# Zigzag_6p_ATtiny_connector.net
KiCad netlist of a schematic drawn in EAGLE
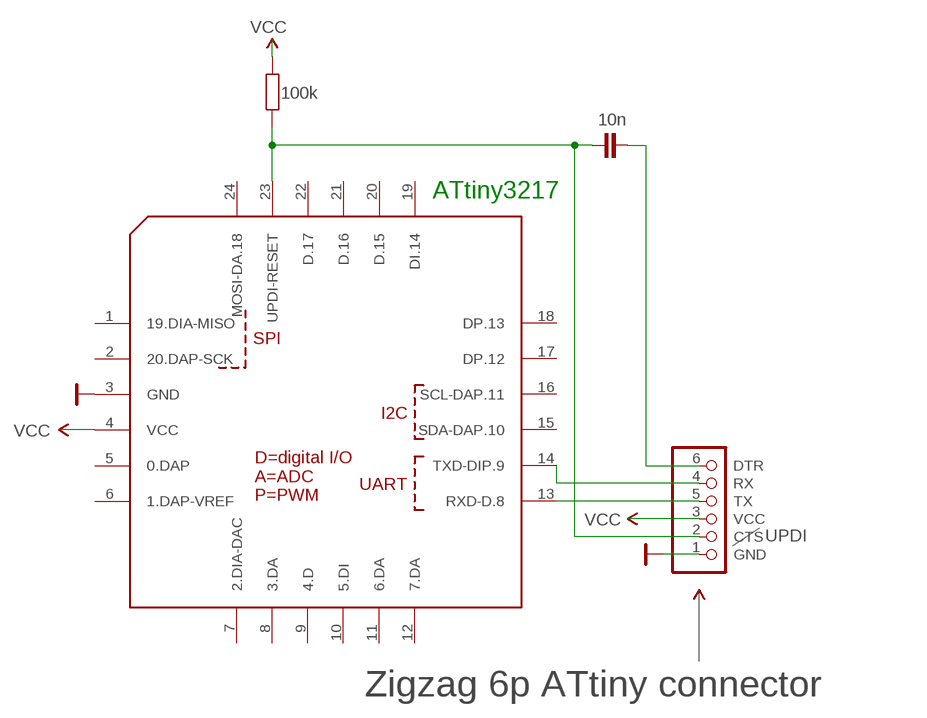
[diagram p0: schematic, sheet 1]

(export (version "E")
  (design (tool "Eeschema 10.0.6"))
  (components
    (comp (ref "C2")
      (value "10n")
      (footprint "eagle-import:0603-SMALL")
      (libsource (lib "eagle-import") (part "SMD-C-0603-SMALL"))
    )
    (comp (ref "J2")
      (value "FTDI")
      (footprint "eagle-import:ZIGZAG-FTDI")
      (libsource (lib "eagle-import") (part "FTDI"))
    )
    (comp (ref "R2")
      (value "100k")
      (footprint "eagle-import:0603-SMALL")
      (libsource (lib "eagle-import") (part "SMD-R0603-S"))
    )
    (comp (ref "U1")
      (value "ATTINY3217-")
      (footprint "eagle-import:QFN-24")
      (libsource (lib "eagle-import") (part "ATTINY3217-"))
    )
  )
  (nets
    (net (code "1") (name "/UPDI") (class "Default")
      (node (ref "C2") (pin "1") (pinfunction "1_1") (pintype "passive"))
      (node (ref "J2") (pin "2") (pinfunction "CTS_2") (pintype "passive"))
      (node (ref "R2") (pin "1") (pinfunction "1_1") (pintype "passive"))
      (node (ref "U1") (pin "23") (pinfunction "UPDI-RESET_23") (pintype "bidirectional"))
    )
    (net (code "2") (name "/VCC") (class "Default")
      (node (ref "J2") (pin "3") (pinfunction "VCC_3") (pintype "passive"))
      (node (ref "R2") (pin "2") (pinfunction "2_2") (pintype "passive"))
      (node (ref "U1") (pin "4") (pinfunction "VCC_4") (pintype "bidirectional"))
    )
    (net (code "3") (name "GND") (class "Default")
      (node (ref "J2") (pin "1") (pinfunction "GND_1") (pintype "passive"))
      (node (ref "U1") (pin "3") (pinfunction "GND_3") (pintype "bidirectional"))
    )
    (net (code "4") (name "Net-(J2-DTR)") (class "Default")
      (node (ref "C2") (pin "2") (pinfunction "2_2") (pintype "passive"))
      (node (ref "J2") (pin "6") (pinfunction "DTR_6") (pintype "passive"))
    )
    (net (code "5") (name "Net-(J2-RX)") (class "Default")
      (node (ref "J2") (pin "4") (pinfunction "RX_4") (pintype "passive"))
      (node (ref "U1") (pin "14") (pinfunction "TXD-DIP.9_14") (pintype "bidirectional"))
    )
    (net (code "6") (name "Net-(J2-TX)") (class "Default")
      (node (ref "J2") (pin "5") (pinfunction "TX_5") (pintype "passive"))
      (node (ref "U1") (pin "13") (pinfunction "RXD-D.8_13") (pintype "bidirectional"))
    )
    (net (code "7") (name "unconnected-(U1-0.DAP-Pad5)") (class "Default")
      (node (ref "U1") (pin "5") (pinfunction "0.DAP_5") (pintype "bidirectional"))
    )
    (net (code "8") (name "unconnected-(U1-1.DAP-VREF-Pad6)") (class "Default")
      (node (ref "U1") (pin "6") (pinfunction "1.DAP-VREF_6") (pintype "bidirectional"))
    )
    (net (code "9") (name "unconnected-(U1-2.DIA-DAC-Pad7)") (class "Default")
      (node (ref "U1") (pin "7") (pinfunction "2.DIA-DAC_7") (pintype "bidirectional"))
    )
    (net (code "10") (name "unconnected-(U1-3.DA-Pad8)") (class "Default")
      (node (ref "U1") (pin "8") (pinfunction "3.DA_8") (pintype "bidirectional"))
    )
    (net (code "11") (name "unconnected-(U1-4.D-Pad9)") (class "Default")
      (node (ref "U1") (pin "9") (pinfunction "4.D_9") (pintype "bidirectional"))
    )
    (net (code "12") (name "unconnected-(U1-5.DI-Pad10)") (class "Default")
      (node (ref "U1") (pin "10") (pinfunction "5.DI_10") (pintype "bidirectional"))
    )
    (net (code "13") (name "unconnected-(U1-6.DA-Pad11)") (class "Default")
      (node (ref "U1") (pin "11") (pinfunction "6.DA_11") (pintype "bidirectional"))
    )
    (net (code "14") (name "unconnected-(U1-7.DA-Pad12)") (class "Default")
      (node (ref "U1") (pin "12") (pinfunction "7.DA_12") (pintype "bidirectional"))
    )
    (net (code "15") (name "unconnected-(U1-19.DIA-MISO-Pad1)") (class "Default")
      (node (ref "U1") (pin "1") (pinfunction "19.DIA-MISO_1") (pintype "bidirectional"))
    )
    (net (code "16") (name "unconnected-(U1-20.DAP-SCK-Pad2)") (class "Default")
      (node (ref "U1") (pin "2") (pinfunction "20.DAP-SCK_2") (pintype "bidirectional"))
    )
    (net (code "17") (name "unconnected-(U1-D.15-Pad20)") (class "Default")
      (node (ref "U1") (pin "20") (pinfunction "D.15_20") (pintype "bidirectional"))
    )
    (net (code "18") (name "unconnected-(U1-D.16-Pad21)") (class "Default")
      (node (ref "U1") (pin "21") (pinfunction "D.16_21") (pintype "bidirectional"))
    )
    (net (code "19") (name "unconnected-(U1-D.17-Pad22)") (class "Default")
      (node (ref "U1") (pin "22") (pinfunction "D.17_22") (pintype "bidirectional"))
    )
    (net (code "20") (name "unconnected-(U1-DI.14-Pad19)") (class "Default")
      (node (ref "U1") (pin "19") (pinfunction "DI.14_19") (pintype "bidirectional"))
    )
    (net (code "21") (name "unconnected-(U1-DP.12-Pad17)") (class "Default")
      (node (ref "U1") (pin "17") (pinfunction "DP.12_17") (pintype "bidirectional"))
    )
    (net (code "22") (name "unconnected-(U1-DP.13-Pad18)") (class "Default")
      (node (ref "U1") (pin "18") (pinfunction "DP.13_18") (pintype "bidirectional"))
    )
    (net (code "23") (name "unconnected-(U1-MOSI-DA.18-Pad24)") (class "Default")
      (node (ref "U1") (pin "24") (pinfunction "MOSI-DA.18_24") (pintype "bidirectional"))
    )
    (net (code "24") (name "unconnected-(U1-SCL-DAP.11-Pad16)") (class "Default")
      (node (ref "U1") (pin "16") (pinfunction "SCL-DAP.11_16") (pintype "bidirectional"))
    )
    (net (code "25") (name "unconnected-(U1-SDA-DAP.10-Pad15)") (class "Default")
      (node (ref "U1") (pin "15") (pinfunction "SDA-DAP.10_15") (pintype "bidirectional"))
    )
  )
)
